# MessstationV2.net
KiCad netlist of a schematic drawn in EAGLE
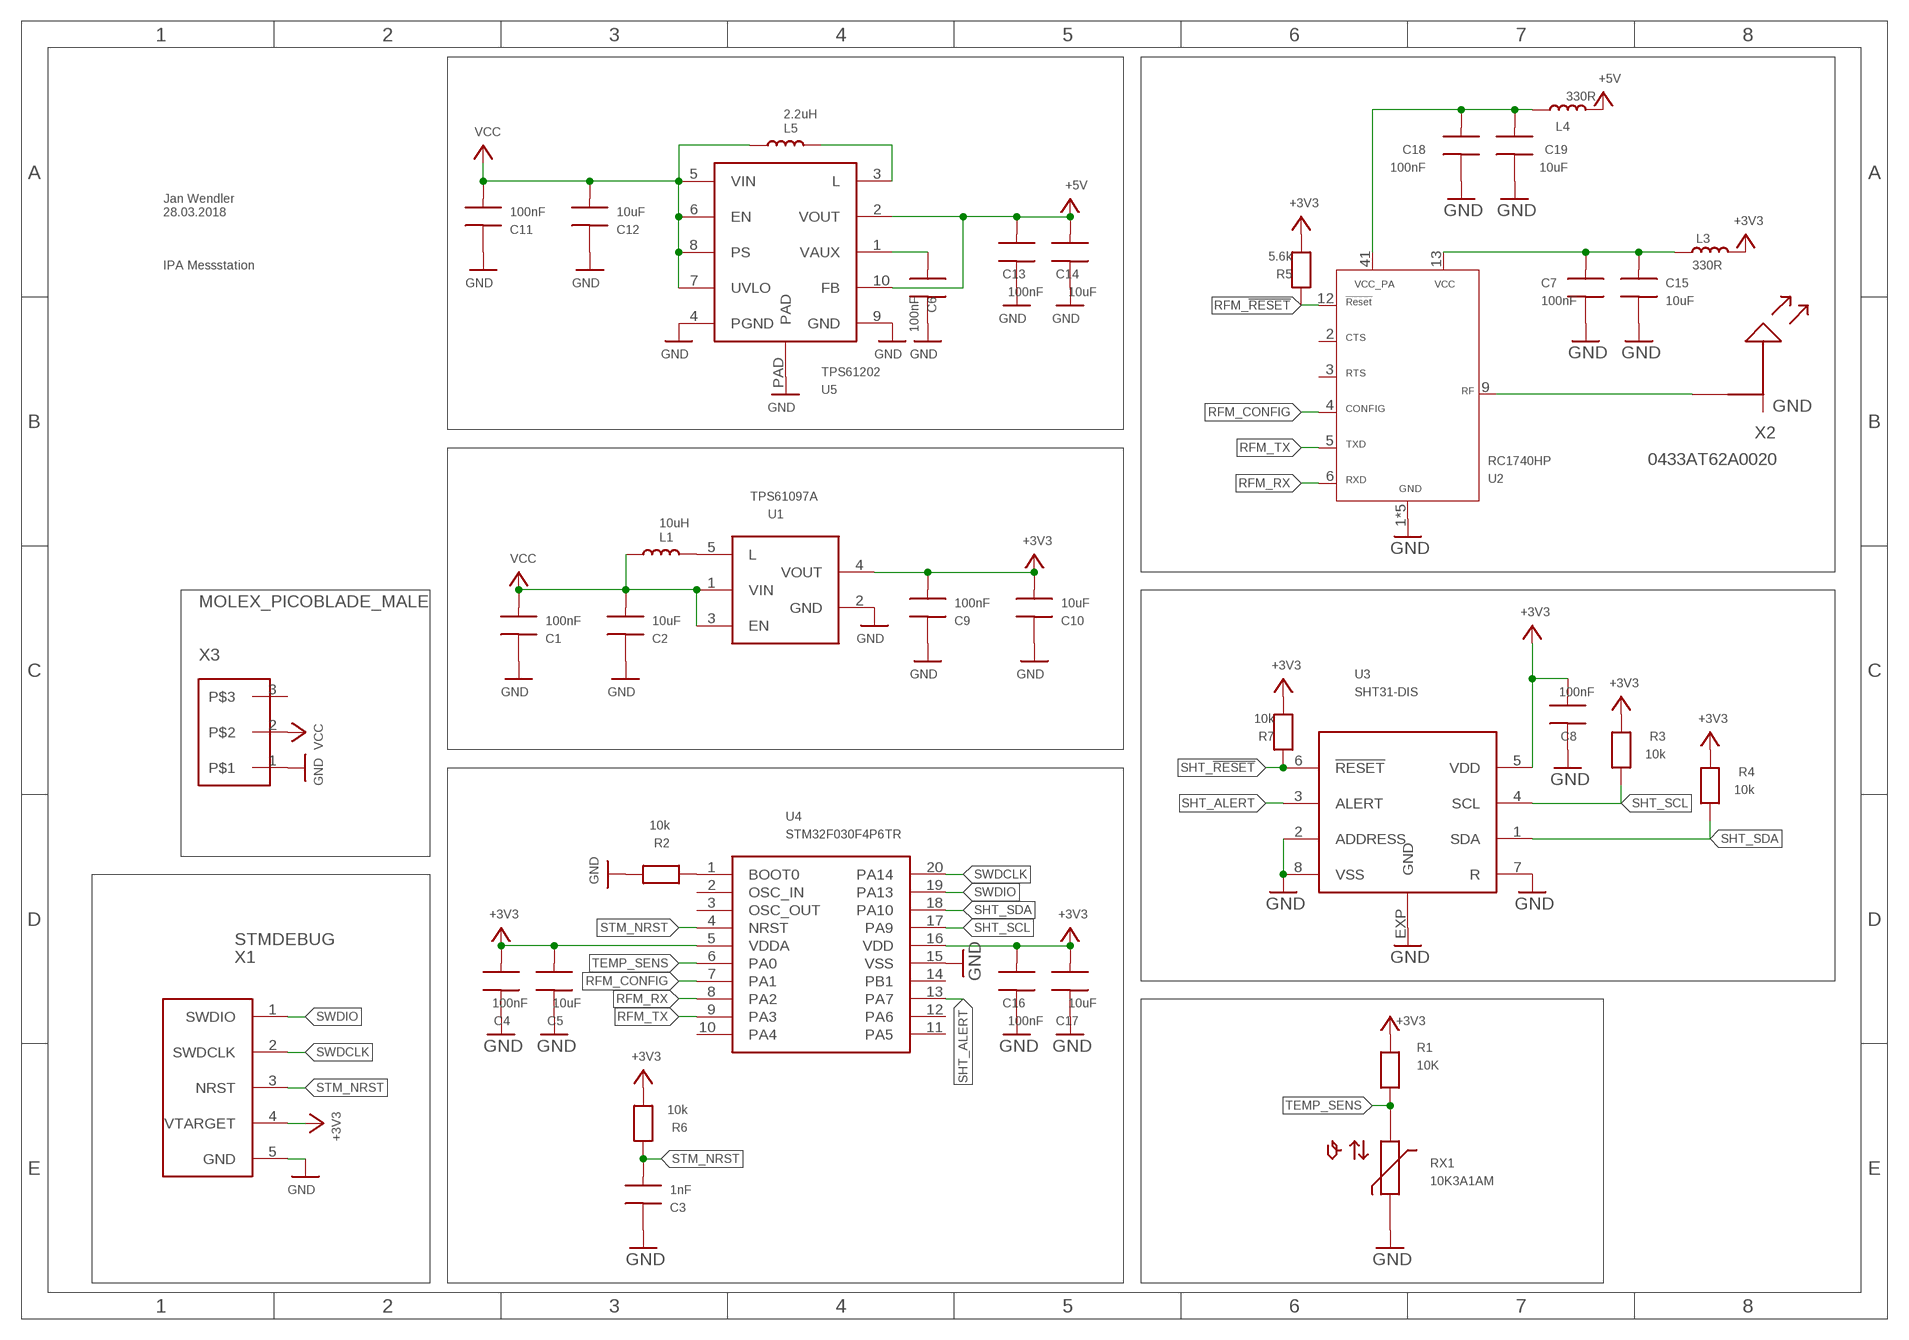
[diagram p0: schematic, sheet 1]

(export (version "E")
  (design (tool "Eeschema 10.0.6"))
  (components
    (comp (ref "C1")
      (value "100nF")
      (footprint "eagle-import:0603")
      (libsource (lib "eagle-import") (part "C0603"))
    )
    (comp (ref "C2")
      (value "10uF")
      (footprint "eagle-import:0603")
      (libsource (lib "eagle-import") (part "C0603"))
    )
    (comp (ref "C3")
      (value "1nF")
      (footprint "eagle-import:0603")
      (libsource (lib "eagle-import") (part "C0603"))
    )
    (comp (ref "C4")
      (value "100nF")
      (footprint "eagle-import:0603")
      (libsource (lib "eagle-import") (part "C0603"))
    )
    (comp (ref "C5")
      (value "10uF")
      (footprint "eagle-import:0603")
      (libsource (lib "eagle-import") (part "C0603"))
    )
    (comp (ref "C6")
      (value "100nF")
      (footprint "eagle-import:0603")
      (libsource (lib "eagle-import") (part "C0603"))
    )
    (comp (ref "C7")
      (value "100nF")
      (footprint "eagle-import:0603")
      (libsource (lib "eagle-import") (part "C0603"))
    )
    (comp (ref "C8")
      (value "100nF")
      (footprint "eagle-import:0603")
      (libsource (lib "eagle-import") (part "C0603"))
    )
    (comp (ref "C9")
      (value "100nF")
      (footprint "eagle-import:0603")
      (libsource (lib "eagle-import") (part "C0603"))
    )
    (comp (ref "C10")
      (value "10uF")
      (footprint "eagle-import:0603")
      (libsource (lib "eagle-import") (part "C0603"))
    )
    (comp (ref "C11")
      (value "100nF")
      (footprint "eagle-import:0603")
      (libsource (lib "eagle-import") (part "C0603"))
    )
    (comp (ref "C12")
      (value "10uF")
      (footprint "eagle-import:0603")
      (libsource (lib "eagle-import") (part "C0603"))
    )
    (comp (ref "C13")
      (value "100nF")
      (footprint "eagle-import:0603")
      (libsource (lib "eagle-import") (part "C0603"))
    )
    (comp (ref "C14")
      (value "10uF")
      (footprint "eagle-import:0603")
      (libsource (lib "eagle-import") (part "C0603"))
    )
    (comp (ref "C15")
      (value "10uF")
      (footprint "eagle-import:0603")
      (libsource (lib "eagle-import") (part "C0603"))
    )
    (comp (ref "C16")
      (value "100nF")
      (footprint "eagle-import:0603")
      (libsource (lib "eagle-import") (part "C0603"))
    )
    (comp (ref "C17")
      (value "10uF")
      (footprint "eagle-import:0603")
      (libsource (lib "eagle-import") (part "C0603"))
    )
    (comp (ref "C18")
      (value "100nF")
      (footprint "eagle-import:0603")
      (libsource (lib "eagle-import") (part "C0603"))
    )
    (comp (ref "C19")
      (value "10uF")
      (footprint "eagle-import:0603")
      (libsource (lib "eagle-import") (part "C0603"))
    )
    (comp (ref "L1")
      (value "10uH")
      (footprint "eagle-import:L10")
      (libsource (lib "eagle-import") (part "L3MM3.3MM"))
    )
    (comp (ref "L3")
      (value "330R")
      (footprint "eagle-import:0603")
      (libsource (lib "eagle-import") (part "L0603"))
    )
    (comp (ref "L4")
      (value "330R")
      (footprint "eagle-import:0603")
      (libsource (lib "eagle-import") (part "L0603"))
    )
    (comp (ref "L5")
      (value "2.2uH")
      (footprint "eagle-import:L2_2")
      (libsource (lib "eagle-import") (part "L3MM2.95MM"))
    )
    (comp (ref "R1")
      (value "10K")
      (footprint "eagle-import:0603")
      (libsource (lib "eagle-import") (part "R0603"))
    )
    (comp (ref "R2")
      (value "10k")
      (footprint "eagle-import:0603")
      (libsource (lib "eagle-import") (part "R0603"))
    )
    (comp (ref "R3")
      (value "10k")
      (footprint "eagle-import:0603")
      (libsource (lib "eagle-import") (part "R0603"))
    )
    (comp (ref "R4")
      (value "10k")
      (footprint "eagle-import:0603")
      (libsource (lib "eagle-import") (part "R0603"))
    )
    (comp (ref "R5")
      (value "5.6k")
      (footprint "eagle-import:0603")
      (libsource (lib "eagle-import") (part "R0603"))
    )
    (comp (ref "R6")
      (value "10k")
      (footprint "eagle-import:0603")
      (libsource (lib "eagle-import") (part "R0603"))
    )
    (comp (ref "R7")
      (value "10k")
      (footprint "eagle-import:0603")
      (libsource (lib "eagle-import") (part "R0603"))
    )
    (comp (ref "RX1")
      (value "10K3A1AM")
      (footprint "eagle-import:TEMPSENS")
      (libsource (lib "eagle-import") (part "10K3A1AM"))
    )
    (comp (ref "U1")
      (value "TPS61097A")
      (footprint "eagle-import:SOT23-5L")
      (libsource (lib "eagle-import") (part "TPS61097A"))
    )
    (comp (ref "U2")
      (value "RC1740HP")
      (footprint "eagle-import:RADIOCRAFTS_MODULE")
      (libsource (lib "eagle-import") (part "RC1740HP"))
    )
    (comp (ref "U3")
      (value "SHT31-DIS")
      (footprint "eagle-import:DFN8-3X3")
      (libsource (lib "eagle-import") (part "SHT31-DIS"))
    )
    (comp (ref "U4")
      (value "STM32F030F4P6TR")
      (footprint "eagle-import:TSSOP20")
      (libsource (lib "eagle-import") (part "STM32F030F4P6TR"))
    )
    (comp (ref "U5")
      (value "TPS61202")
      (footprint "eagle-import:VSON10")
      (libsource (lib "eagle-import") (part "TPS61202"))
    )
    (comp (ref "X1")
      (value "STMDEBUG")
      (footprint "eagle-import:STIFTLEISTE1X5")
      (libsource (lib "eagle-import") (part "STMDEBUG"))
    )
    (comp (ref "X2")
      (value "0433AT62A0020")
      (footprint "eagle-import:ANTENNE_CON")
      (libsource (lib "eagle-import") (part "0433AT62A0020"))
    )
    (comp (ref "X3")
      (value "MOLEX_PICOBLADE_MALE")
      (footprint "eagle-import:MOLEX_PICOBLADE_MALE")
      (libsource (lib "eagle-import") (part "MOLEX_PICOBLADE_MALE"))
    )
  )
  (nets
    (net (code "1") (name "+3V3") (class "Default")
      (node (ref "C10") (pin "1") (pinfunction "P$1_1") (pintype "bidirectional"))
      (node (ref "C16") (pin "1") (pinfunction "P$1_1") (pintype "bidirectional"))
      (node (ref "C17") (pin "1") (pinfunction "P$1_1") (pintype "bidirectional"))
      (node (ref "C4") (pin "1") (pinfunction "P$1_1") (pintype "bidirectional"))
      (node (ref "C5") (pin "1") (pinfunction "P$1_1") (pintype "bidirectional"))
      (node (ref "C8") (pin "1") (pinfunction "P$1_1") (pintype "bidirectional"))
      (node (ref "C9") (pin "1") (pinfunction "P$1_1") (pintype "bidirectional"))
      (node (ref "L3") (pin "1") (pinfunction "P$1_1") (pintype "bidirectional"))
      (node (ref "R1") (pin "2") (pinfunction "P$2_2") (pintype "bidirectional"))
      (node (ref "R3") (pin "2") (pinfunction "P$2_2") (pintype "bidirectional"))
      (node (ref "R4") (pin "2") (pinfunction "P$2_2") (pintype "bidirectional"))
      (node (ref "R5") (pin "1") (pinfunction "P$1_1") (pintype "bidirectional"))
      (node (ref "R6") (pin "1") (pinfunction "P$1_1") (pintype "bidirectional"))
      (node (ref "R7") (pin "1") (pinfunction "P$1_1") (pintype "bidirectional"))
      (node (ref "U1") (pin "4") (pinfunction "VOUT_4") (pintype "bidirectional"))
      (node (ref "U3") (pin "5") (pinfunction "VDD_5") (pintype "bidirectional"))
      (node (ref "U4") (pin "16") (pinfunction "VDD_16") (pintype "bidirectional"))
      (node (ref "U4") (pin "5") (pinfunction "VDDA_5") (pintype "bidirectional"))
      (node (ref "X1") (pin "4") (pinfunction "VTARGET_4") (pintype "bidirectional"))
    )
    (net (code "2") (name "+5V") (class "Default")
      (node (ref "C13") (pin "1") (pinfunction "P$1_1") (pintype "bidirectional"))
      (node (ref "C14") (pin "1") (pinfunction "P$1_1") (pintype "bidirectional"))
      (node (ref "L4") (pin "1") (pinfunction "P$1_1") (pintype "bidirectional"))
      (node (ref "U5") (pin "10") (pinfunction "FB_10") (pintype "bidirectional"))
      (node (ref "U5") (pin "2") (pinfunction "VOUT_2") (pintype "bidirectional"))
    )
    (net (code "3") (name "/RFM_~{RESET}") (class "Default")
      (node (ref "R5") (pin "2") (pinfunction "P$2_2") (pintype "bidirectional"))
      (node (ref "U2") (pin "12") (pinfunction "~{RESET}_12") (pintype "bidirectional"))
    )
    (net (code "4") (name "/SHT_~{RESET}") (class "Default")
      (node (ref "R7") (pin "2") (pinfunction "P$2_2") (pintype "bidirectional"))
      (node (ref "U3") (pin "6") (pinfunction "~{RESET}_6") (pintype "bidirectional"))
    )
    (net (code "5") (name "GND") (class "Default")
      (node (ref "C1") (pin "2") (pinfunction "P$2_2") (pintype "bidirectional"))
      (node (ref "C10") (pin "2") (pinfunction "P$2_2") (pintype "bidirectional"))
      (node (ref "C11") (pin "2") (pinfunction "P$2_2") (pintype "bidirectional"))
      (node (ref "C12") (pin "2") (pinfunction "P$2_2") (pintype "bidirectional"))
      (node (ref "C13") (pin "2") (pinfunction "P$2_2") (pintype "bidirectional"))
      (node (ref "C14") (pin "2") (pinfunction "P$2_2") (pintype "bidirectional"))
      (node (ref "C15") (pin "2") (pinfunction "P$2_2") (pintype "bidirectional"))
      (node (ref "C16") (pin "2") (pinfunction "P$2_2") (pintype "bidirectional"))
      (node (ref "C17") (pin "2") (pinfunction "P$2_2") (pintype "bidirectional"))
      (node (ref "C18") (pin "2") (pinfunction "P$2_2") (pintype "bidirectional"))
      (node (ref "C19") (pin "2") (pinfunction "P$2_2") (pintype "bidirectional"))
      (node (ref "C2") (pin "2") (pinfunction "P$2_2") (pintype "bidirectional"))
      (node (ref "C3") (pin "2") (pinfunction "P$2_2") (pintype "bidirectional"))
      (node (ref "C4") (pin "2") (pinfunction "P$2_2") (pintype "bidirectional"))
      (node (ref "C5") (pin "2") (pinfunction "P$2_2") (pintype "bidirectional"))
      (node (ref "C6") (pin "2") (pinfunction "P$2_2") (pintype "bidirectional"))
      (node (ref "C7") (pin "2") (pinfunction "P$2_2") (pintype "bidirectional"))
      (node (ref "C8") (pin "2") (pinfunction "P$2_2") (pintype "bidirectional"))
      (node (ref "C9") (pin "2") (pinfunction "P$2_2") (pintype "bidirectional"))
      (node (ref "R2") (pin "2") (pinfunction "P$2_2") (pintype "bidirectional"))
      (node (ref "RX1") (pin "P$3") (pinfunction "P$2_P$3") (pintype "bidirectional"))
      (node (ref "U1") (pin "2") (pinfunction "GND_2") (pintype "bidirectional"))
      (node (ref "U2") (pin "1") (pinfunction "GND_1") (pintype "bidirectional"))
      (node (ref "U2") (pin "10") (pinfunction "GND_10") (pintype "bidirectional"))
      (node (ref "U2") (pin "14") (pinfunction "GND_14") (pintype "bidirectional"))
      (node (ref "U2") (pin "7") (pinfunction "GND_7") (pintype "bidirectional"))
      (node (ref "U2") (pin "8") (pinfunction "GND_8") (pintype "bidirectional"))
      (node (ref "U3") (pin "2") (pinfunction "ADDRESS_2") (pintype "bidirectional"))
      (node (ref "U3") (pin "7") (pinfunction "R_7") (pintype "bidirectional"))
      (node (ref "U3") (pin "8") (pinfunction "VSS_8") (pintype "bidirectional"))
      (node (ref "U3") (pin "EXP") (pinfunction "GND_EXP") (pintype "bidirectional"))
      (node (ref "U4") (pin "15") (pinfunction "VSS_15") (pintype "bidirectional"))
      (node (ref "U5") (pin "4") (pinfunction "PGND_4") (pintype "bidirectional"))
      (node (ref "U5") (pin "9") (pinfunction "GND_9") (pintype "bidirectional"))
      (node (ref "U5") (pin "PAD") (pinfunction "PAD_PAD") (pintype "bidirectional"))
      (node (ref "X1") (pin "5") (pinfunction "GND_5") (pintype "bidirectional"))
      (node (ref "X3") (pin "1") (pinfunction "P$1_1") (pintype "bidirectional"))
    )
    (net (code "6") (name "Net-(C6-P$1)") (class "Default")
      (node (ref "C6") (pin "1") (pinfunction "P$1_1") (pintype "bidirectional"))
      (node (ref "U5") (pin "1") (pinfunction "VAUX_1") (pintype "bidirectional"))
    )
    (net (code "7") (name "Net-(C15-P$1)") (class "Default")
      (node (ref "C15") (pin "1") (pinfunction "P$1_1") (pintype "bidirectional"))
      (node (ref "C7") (pin "1") (pinfunction "P$1_1") (pintype "bidirectional"))
      (node (ref "L3") (pin "2") (pinfunction "P$2_2") (pintype "bidirectional"))
      (node (ref "U2") (pin "13") (pinfunction "VCC_13") (pintype "bidirectional"))
    )
    (net (code "8") (name "Net-(C18-P$1)") (class "Default")
      (node (ref "C18") (pin "1") (pinfunction "P$1_1") (pintype "bidirectional"))
      (node (ref "C19") (pin "1") (pinfunction "P$1_1") (pintype "bidirectional"))
      (node (ref "L4") (pin "2") (pinfunction "P$2_2") (pintype "bidirectional"))
      (node (ref "U2") (pin "41") (pinfunction "VCC_PA_41") (pintype "bidirectional"))
    )
    (net (code "9") (name "Net-(R2-P$1)") (class "Default")
      (node (ref "R2") (pin "1") (pinfunction "P$1_1") (pintype "bidirectional"))
      (node (ref "U4") (pin "1") (pinfunction "BOOT0_1") (pintype "bidirectional"))
    )
    (net (code "10") (name "Net-(U1-L)") (class "Default")
      (node (ref "L1") (pin "P$1") (pinfunction "P$1_P$1") (pintype "bidirectional"))
      (node (ref "U1") (pin "5") (pinfunction "L_5") (pintype "bidirectional"))
    )
    (net (code "11") (name "Net-(U2-RF)") (class "Default")
      (node (ref "U2") (pin "9") (pinfunction "RF_9") (pintype "bidirectional"))
      (node (ref "X2") (pin "P$1") (pinfunction "P$1_P$1") (pintype "bidirectional"))
    )
    (net (code "12") (name "Net-(U5-L)") (class "Default")
      (node (ref "L5") (pin "P$1") (pinfunction "P$1_P$1") (pintype "bidirectional"))
      (node (ref "U5") (pin "3") (pinfunction "L_3") (pintype "bidirectional"))
    )
    (net (code "13") (name "RFM_CONFIG") (class "Default")
      (node (ref "U2") (pin "4") (pinfunction "CONFIG_4") (pintype "bidirectional"))
      (node (ref "U4") (pin "7") (pinfunction "PA1_7") (pintype "bidirectional"))
    )
    (net (code "14") (name "RFM_RX") (class "Default")
      (node (ref "U2") (pin "6") (pinfunction "RXD_6") (pintype "bidirectional"))
      (node (ref "U4") (pin "8") (pinfunction "PA2_8") (pintype "bidirectional"))
    )
    (net (code "15") (name "RFM_TX") (class "Default")
      (node (ref "U2") (pin "5") (pinfunction "TXD_5") (pintype "bidirectional"))
      (node (ref "U4") (pin "9") (pinfunction "PA3_9") (pintype "bidirectional"))
    )
    (net (code "16") (name "SHT_ALERT") (class "Default")
      (node (ref "U3") (pin "3") (pinfunction "ALERT_3") (pintype "bidirectional"))
      (node (ref "U4") (pin "13") (pinfunction "PA7_13") (pintype "bidirectional"))
    )
    (net (code "17") (name "SHT_SCL") (class "Default")
      (node (ref "R3") (pin "1") (pinfunction "P$1_1") (pintype "bidirectional"))
      (node (ref "U3") (pin "4") (pinfunction "SCL_4") (pintype "bidirectional"))
      (node (ref "U4") (pin "17") (pinfunction "PA9_17") (pintype "bidirectional"))
    )
    (net (code "18") (name "SHT_SDA") (class "Default")
      (node (ref "R4") (pin "1") (pinfunction "P$1_1") (pintype "bidirectional"))
      (node (ref "U3") (pin "1") (pinfunction "SDA_1") (pintype "bidirectional"))
      (node (ref "U4") (pin "18") (pinfunction "PA10_18") (pintype "bidirectional"))
    )
    (net (code "19") (name "STM_NRST") (class "Default")
      (node (ref "C3") (pin "1") (pinfunction "P$1_1") (pintype "bidirectional"))
      (node (ref "R6") (pin "2") (pinfunction "P$2_2") (pintype "bidirectional"))
      (node (ref "U4") (pin "4") (pinfunction "NRST_4") (pintype "bidirectional"))
      (node (ref "X1") (pin "3") (pinfunction "NRST_3") (pintype "bidirectional"))
    )
    (net (code "20") (name "SWDCLK") (class "Default")
      (node (ref "U4") (pin "20") (pinfunction "PA14_20") (pintype "bidirectional"))
      (node (ref "X1") (pin "2") (pinfunction "SWDCLK_2") (pintype "bidirectional"))
    )
    (net (code "21") (name "SWDIO") (class "Default")
      (node (ref "U4") (pin "19") (pinfunction "PA13_19") (pintype "bidirectional"))
      (node (ref "X1") (pin "1") (pinfunction "SWDIO_1") (pintype "bidirectional"))
    )
    (net (code "22") (name "TEMP_SENS") (class "Default")
      (node (ref "R1") (pin "1") (pinfunction "P$1_1") (pintype "bidirectional"))
      (node (ref "RX1") (pin "P$4") (pinfunction "P$1_P$4") (pintype "bidirectional"))
      (node (ref "U4") (pin "6") (pinfunction "PA0_6") (pintype "bidirectional"))
    )
    (net (code "23") (name "VCC") (class "Default")
      (node (ref "C1") (pin "1") (pinfunction "P$1_1") (pintype "bidirectional"))
      (node (ref "C11") (pin "1") (pinfunction "P$1_1") (pintype "bidirectional"))
      (node (ref "C12") (pin "1") (pinfunction "P$1_1") (pintype "bidirectional"))
      (node (ref "C2") (pin "1") (pinfunction "P$1_1") (pintype "bidirectional"))
      (node (ref "L1") (pin "P$2") (pinfunction "P$2_P$2") (pintype "bidirectional"))
      (node (ref "L5") (pin "P$2") (pinfunction "P$2_P$2") (pintype "bidirectional"))
      (node (ref "U1") (pin "1") (pinfunction "VIN_1") (pintype "bidirectional"))
      (node (ref "U1") (pin "3") (pinfunction "EN_3") (pintype "bidirectional"))
      (node (ref "U5") (pin "5") (pinfunction "VIN_5") (pintype "bidirectional"))
      (node (ref "U5") (pin "6") (pinfunction "EN_6") (pintype "bidirectional"))
      (node (ref "U5") (pin "7") (pinfunction "UVLO_7") (pintype "bidirectional"))
      (node (ref "U5") (pin "8") (pinfunction "PS_8") (pintype "bidirectional"))
      (node (ref "X3") (pin "2") (pinfunction "P$2_2") (pintype "bidirectional"))
    )
    (net (code "24") (name "unconnected-(U2-CTS-Pad2)") (class "Default")
      (node (ref "U2") (pin "2") (pinfunction "CTS_2") (pintype "bidirectional"))
    )
    (net (code "25") (name "unconnected-(U2-RTS-Pad3)") (class "Default")
      (node (ref "U2") (pin "3") (pinfunction "RTS_3") (pintype "bidirectional"))
    )
    (net (code "26") (name "unconnected-(U4-OSC_IN-Pad2)") (class "Default")
      (node (ref "U4") (pin "2") (pinfunction "OSC_IN_2") (pintype "bidirectional"))
    )
    (net (code "27") (name "unconnected-(U4-OSC_OUT-Pad3)") (class "Default")
      (node (ref "U4") (pin "3") (pinfunction "OSC_OUT_3") (pintype "bidirectional"))
    )
    (net (code "28") (name "unconnected-(U4-PA4-Pad10)") (class "Default")
      (node (ref "U4") (pin "10") (pinfunction "PA4_10") (pintype "bidirectional"))
    )
    (net (code "29") (name "unconnected-(U4-PA5-Pad11)") (class "Default")
      (node (ref "U4") (pin "11") (pinfunction "PA5_11") (pintype "bidirectional"))
    )
    (net (code "30") (name "unconnected-(U4-PA6-Pad12)") (class "Default")
      (node (ref "U4") (pin "12") (pinfunction "PA6_12") (pintype "bidirectional"))
    )
    (net (code "31") (name "unconnected-(U4-PB1-Pad14)") (class "Default")
      (node (ref "U4") (pin "14") (pinfunction "PB1_14") (pintype "bidirectional"))
    )
    (net (code "32") (name "unconnected-(X2-GND-PadP$2)") (class "Default")
      (node (ref "X2") (pin "P$2") (pinfunction "GND_P$2") (pintype "bidirectional"))
    )
    (net (code "33") (name "unconnected-(X3-P$3-Pad3)") (class "Default")
      (node (ref "X3") (pin "3") (pinfunction "P$3_3") (pintype "bidirectional"))
    )
  )
)
